# Busboard_SCH.net
KiCad netlist of a schematic drawn in Altium Designer
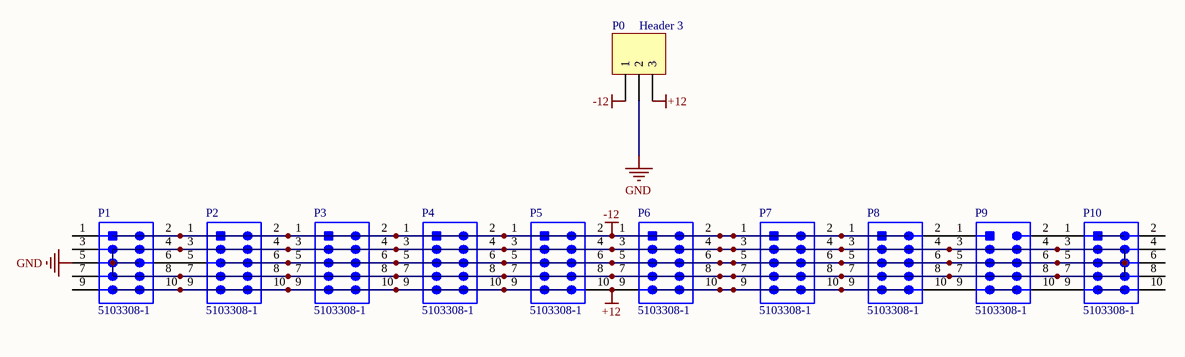
[diagram p0: Busboard_SCH.SchDoc]

(export (version "E")
  (design (tool "Eeschema 10.0.6"))
  (components
    (comp (ref "P0")
      (value "Header 3")
      (footprint "HDR1X3")
      (description "Header, 3-Pin")
      (fields (field (name "PUBLISHER") "Altium Limited"))
      (libsource (lib "Miscellaneous Connectors") (part "Header 3"))
    )
    (comp (ref "P1")
      (value "5103308-1")
      (footprint "TECO-5103308-1_V")
      (description "Male Header, Pitch 2.54 mm, 2 x 5 Position, Height 9.85 mm, Tail Length 3.05 mm, RoHS, Tube")
      (fields (field (name "MANUFACTURER") "TE Connectivity"))
      (libsource (lib "Altium Content Vault") (part "CN-2P-M-R10"))
    )
    (comp (ref "P2")
      (value "5103308-1")
      (footprint "TECO-5103308-1_V")
      (description "Male Header, Pitch 2.54 mm, 2 x 5 Position, Height 9.85 mm, Tail Length 3.05 mm, RoHS, Tube")
      (fields (field (name "MANUFACTURER") "TE Connectivity"))
      (libsource (lib "Altium Content Vault") (part "CN-2P-M-R10"))
    )
    (comp (ref "P3")
      (value "5103308-1")
      (footprint "TECO-5103308-1_V")
      (description "Male Header, Pitch 2.54 mm, 2 x 5 Position, Height 9.85 mm, Tail Length 3.05 mm, RoHS, Tube")
      (fields (field (name "MANUFACTURER") "TE Connectivity"))
      (libsource (lib "Altium Content Vault") (part "CN-2P-M-R10"))
    )
    (comp (ref "P4")
      (value "5103308-1")
      (footprint "TECO-5103308-1_V")
      (description "Male Header, Pitch 2.54 mm, 2 x 5 Position, Height 9.85 mm, Tail Length 3.05 mm, RoHS, Tube")
      (fields (field (name "MANUFACTURER") "TE Connectivity"))
      (libsource (lib "Altium Content Vault") (part "CN-2P-M-R10"))
    )
    (comp (ref "P5")
      (value "5103308-1")
      (footprint "TECO-5103308-1_V")
      (description "Male Header, Pitch 2.54 mm, 2 x 5 Position, Height 9.85 mm, Tail Length 3.05 mm, RoHS, Tube")
      (fields (field (name "MANUFACTURER") "TE Connectivity"))
      (libsource (lib "Altium Content Vault") (part "CN-2P-M-R10"))
    )
    (comp (ref "P6")
      (value "5103308-1")
      (footprint "TECO-5103308-1_V")
      (description "Male Header, Pitch 2.54 mm, 2 x 5 Position, Height 9.85 mm, Tail Length 3.05 mm, RoHS, Tube")
      (fields (field (name "MANUFACTURER") "TE Connectivity"))
      (libsource (lib "Altium Content Vault") (part "CN-2P-M-R10"))
    )
    (comp (ref "P7")
      (value "5103308-1")
      (footprint "TECO-5103308-1_V")
      (description "Male Header, Pitch 2.54 mm, 2 x 5 Position, Height 9.85 mm, Tail Length 3.05 mm, RoHS, Tube")
      (fields (field (name "MANUFACTURER") "TE Connectivity"))
      (libsource (lib "Altium Content Vault") (part "CN-2P-M-R10"))
    )
    (comp (ref "P8")
      (value "5103308-1")
      (footprint "TECO-5103308-1_V")
      (description "Male Header, Pitch 2.54 mm, 2 x 5 Position, Height 9.85 mm, Tail Length 3.05 mm, RoHS, Tube")
      (fields (field (name "MANUFACTURER") "TE Connectivity"))
      (libsource (lib "Altium Content Vault") (part "CN-2P-M-R10"))
    )
    (comp (ref "P9")
      (value "5103308-1")
      (footprint "TECO-5103308-1_V")
      (description "Male Header, Pitch 2.54 mm, 2 x 5 Position, Height 9.85 mm, Tail Length 3.05 mm, RoHS, Tube")
      (fields (field (name "MANUFACTURER") "TE Connectivity"))
      (libsource (lib "Altium Content Vault") (part "CN-2P-M-R10"))
    )
    (comp (ref "P10")
      (value "5103308-1")
      (footprint "TECO-5103308-1_V")
      (description "Male Header, Pitch 2.54 mm, 2 x 5 Position, Height 9.85 mm, Tail Length 3.05 mm, RoHS, Tube")
      (fields (field (name "MANUFACTURER") "TE Connectivity"))
      (libsource (lib "Altium Content Vault") (part "CN-2P-M-R10"))
    )
  )
  (nets
    (net (code "1") (name "+12") (class "Default")
      (node (ref "P0") (pin "3") (pinfunction "3_3") (pintype "passive"))
      (node (ref "P5") (pin "10") (pinfunction "10_10") (pintype "passive"))
      (node (ref "P6") (pin "9") (pinfunction "9_9") (pintype "passive"))
    )
    (net (code "2") (name "-12") (class "Default")
      (node (ref "P0") (pin "1") (pinfunction "1_1") (pintype "passive"))
      (node (ref "P1") (pin "2") (pinfunction "2_2") (pintype "passive"))
      (node (ref "P2") (pin "1") (pinfunction "1_1") (pintype "passive"))
      (node (ref "P2") (pin "2") (pinfunction "2_2") (pintype "passive"))
      (node (ref "P3") (pin "1") (pinfunction "1_1") (pintype "passive"))
      (node (ref "P3") (pin "2") (pinfunction "2_2") (pintype "passive"))
      (node (ref "P4") (pin "1") (pinfunction "1_1") (pintype "passive"))
      (node (ref "P4") (pin "2") (pinfunction "2_2") (pintype "passive"))
      (node (ref "P5") (pin "1") (pinfunction "1_1") (pintype "passive"))
      (node (ref "P5") (pin "2") (pinfunction "2_2") (pintype "passive"))
      (node (ref "P6") (pin "1") (pinfunction "1_1") (pintype "passive"))
      (node (ref "P6") (pin "2") (pinfunction "2_2") (pintype "passive"))
      (node (ref "P7") (pin "1") (pinfunction "1_1") (pintype "passive"))
      (node (ref "P7") (pin "2") (pinfunction "2_2") (pintype "passive"))
      (node (ref "P8") (pin "1") (pinfunction "1_1") (pintype "passive"))
    )
    (net (code "3") (name "GND") (class "Default")
      (node (ref "P0") (pin "2") (pinfunction "2_2") (pintype "passive"))
      (node (ref "P1") (pin "5") (pinfunction "5_5") (pintype "passive"))
    )
    (net (code "4") (name "Net-(P1-Pad4)") (class "Default")
      (node (ref "P1") (pin "4") (pinfunction "4_4") (pintype "passive"))
      (node (ref "P1") (pin "8") (pinfunction "8_8") (pintype "passive"))
      (node (ref "P10") (pin "3") (pinfunction "3_3") (pintype "passive"))
      (node (ref "P10") (pin "5") (pinfunction "5_5") (pintype "passive"))
      (node (ref "P10") (pin "7") (pinfunction "7_7") (pintype "passive"))
      (node (ref "P2") (pin "3") (pinfunction "3_3") (pintype "passive"))
      (node (ref "P2") (pin "4") (pinfunction "4_4") (pintype "passive"))
      (node (ref "P2") (pin "6") (pinfunction "6_6") (pintype "passive"))
      (node (ref "P2") (pin "7") (pinfunction "7_7") (pintype "passive"))
      (node (ref "P2") (pin "8") (pinfunction "8_8") (pintype "passive"))
      (node (ref "P3") (pin "3") (pinfunction "3_3") (pintype "passive"))
      (node (ref "P3") (pin "4") (pinfunction "4_4") (pintype "passive"))
      (node (ref "P3") (pin "5") (pinfunction "5_5") (pintype "passive"))
      (node (ref "P3") (pin "6") (pinfunction "6_6") (pintype "passive"))
      (node (ref "P3") (pin "7") (pinfunction "7_7") (pintype "passive"))
      (node (ref "P3") (pin "8") (pinfunction "8_8") (pintype "passive"))
      (node (ref "P4") (pin "3") (pinfunction "3_3") (pintype "passive"))
      (node (ref "P4") (pin "4") (pinfunction "4_4") (pintype "passive"))
      (node (ref "P4") (pin "5") (pinfunction "5_5") (pintype "passive"))
      (node (ref "P4") (pin "6") (pinfunction "6_6") (pintype "passive"))
      (node (ref "P4") (pin "7") (pinfunction "7_7") (pintype "passive"))
      (node (ref "P4") (pin "8") (pinfunction "8_8") (pintype "passive"))
      (node (ref "P5") (pin "3") (pinfunction "3_3") (pintype "passive"))
      (node (ref "P5") (pin "4") (pinfunction "4_4") (pintype "passive"))
      (node (ref "P5") (pin "5") (pinfunction "5_5") (pintype "passive"))
      (node (ref "P5") (pin "6") (pinfunction "6_6") (pintype "passive"))
      (node (ref "P5") (pin "7") (pinfunction "7_7") (pintype "passive"))
      (node (ref "P5") (pin "8") (pinfunction "8_8") (pintype "passive"))
      (node (ref "P6") (pin "3") (pinfunction "3_3") (pintype "passive"))
      (node (ref "P6") (pin "4") (pinfunction "4_4") (pintype "passive"))
      (node (ref "P6") (pin "5") (pinfunction "5_5") (pintype "passive"))
      (node (ref "P6") (pin "6") (pinfunction "6_6") (pintype "passive"))
      (node (ref "P6") (pin "7") (pinfunction "7_7") (pintype "passive"))
      (node (ref "P6") (pin "8") (pinfunction "8_8") (pintype "passive"))
      (node (ref "P7") (pin "3") (pinfunction "3_3") (pintype "passive"))
      (node (ref "P7") (pin "4") (pinfunction "4_4") (pintype "passive"))
      (node (ref "P7") (pin "5") (pinfunction "5_5") (pintype "passive"))
      (node (ref "P7") (pin "6") (pinfunction "6_6") (pintype "passive"))
      (node (ref "P7") (pin "7") (pinfunction "7_7") (pintype "passive"))
      (node (ref "P7") (pin "8") (pinfunction "8_8") (pintype "passive"))
      (node (ref "P8") (pin "3") (pinfunction "3_3") (pintype "passive"))
      (node (ref "P8") (pin "4") (pinfunction "4_4") (pintype "passive"))
      (node (ref "P8") (pin "5") (pinfunction "5_5") (pintype "passive"))
      (node (ref "P8") (pin "6") (pinfunction "6_6") (pintype "passive"))
      (node (ref "P8") (pin "7") (pinfunction "7_7") (pintype "passive"))
      (node (ref "P8") (pin "8") (pinfunction "8_8") (pintype "passive"))
      (node (ref "P9") (pin "3") (pinfunction "3_3") (pintype "passive"))
      (node (ref "P9") (pin "4") (pinfunction "4_4") (pintype "passive"))
      (node (ref "P9") (pin "5") (pinfunction "5_5") (pintype "passive"))
      (node (ref "P9") (pin "6") (pinfunction "6_6") (pintype "passive"))
      (node (ref "P9") (pin "7") (pinfunction "7_7") (pintype "passive"))
      (node (ref "P9") (pin "8") (pinfunction "8_8") (pintype "passive"))
    )
    (net (code "5") (name "Net-(P1-Pad6)") (class "Default")
      (node (ref "P1") (pin "6") (pinfunction "6_6") (pintype "passive"))
      (node (ref "P2") (pin "5") (pinfunction "5_5") (pintype "passive"))
    )
    (net (code "6") (name "Net-(P1-Pad10)") (class "Default")
      (node (ref "P1") (pin "10") (pinfunction "10_10") (pintype "passive"))
      (node (ref "P2") (pin "10") (pinfunction "10_10") (pintype "passive"))
      (node (ref "P2") (pin "9") (pinfunction "9_9") (pintype "passive"))
      (node (ref "P3") (pin "10") (pinfunction "10_10") (pintype "passive"))
      (node (ref "P3") (pin "9") (pinfunction "9_9") (pintype "passive"))
      (node (ref "P4") (pin "10") (pinfunction "10_10") (pintype "passive"))
      (node (ref "P4") (pin "9") (pinfunction "9_9") (pintype "passive"))
      (node (ref "P5") (pin "9") (pinfunction "9_9") (pintype "passive"))
    )
    (net (code "7") (name "Net-(P6-Pad10)") (class "Default")
      (node (ref "P6") (pin "10") (pinfunction "10_10") (pintype "passive"))
      (node (ref "P7") (pin "10") (pinfunction "10_10") (pintype "passive"))
      (node (ref "P7") (pin "9") (pinfunction "9_9") (pintype "passive"))
      (node (ref "P8") (pin "9") (pinfunction "9_9") (pintype "passive"))
    )
    (net (code "8") (name "Net-(P8-Pad2)") (class "Default")
      (node (ref "P8") (pin "2") (pinfunction "2_2") (pintype "passive"))
      (node (ref "P9") (pin "1") (pinfunction "1_1") (pintype "passive"))
    )
    (net (code "9") (name "Net-(P8-Pad10)") (class "Default")
      (node (ref "P8") (pin "10") (pinfunction "10_10") (pintype "passive"))
      (node (ref "P9") (pin "9") (pinfunction "9_9") (pintype "passive"))
    )
    (net (code "10") (name "Net-(P10-Pad1)") (class "Default")
      (node (ref "P10") (pin "1") (pinfunction "1_1") (pintype "passive"))
      (node (ref "P9") (pin "2") (pinfunction "2_2") (pintype "passive"))
    )
    (net (code "11") (name "Net-(P10-Pad9)") (class "Default")
      (node (ref "P10") (pin "9") (pinfunction "9_9") (pintype "passive"))
      (node (ref "P9") (pin "10") (pinfunction "10_10") (pintype "passive"))
    )
    (net (code "12") (name "unconnected-(P1-Pad1)") (class "Default")
      (node (ref "P1") (pin "1") (pinfunction "1_1") (pintype "passive"))
    )
    (net (code "13") (name "unconnected-(P1-Pad3)") (class "Default")
      (node (ref "P1") (pin "3") (pinfunction "3_3") (pintype "passive"))
    )
    (net (code "14") (name "unconnected-(P1-Pad7)") (class "Default")
      (node (ref "P1") (pin "7") (pinfunction "7_7") (pintype "passive"))
    )
    (net (code "15") (name "unconnected-(P1-Pad9)") (class "Default")
      (node (ref "P1") (pin "9") (pinfunction "9_9") (pintype "passive"))
    )
    (net (code "16") (name "unconnected-(P10-Pad2)") (class "Default")
      (node (ref "P10") (pin "2") (pinfunction "2_2") (pintype "passive"))
    )
    (net (code "17") (name "unconnected-(P10-Pad4)") (class "Default")
      (node (ref "P10") (pin "4") (pinfunction "4_4") (pintype "passive"))
    )
    (net (code "18") (name "unconnected-(P10-Pad6)") (class "Default")
      (node (ref "P10") (pin "6") (pinfunction "6_6") (pintype "passive"))
    )
    (net (code "19") (name "unconnected-(P10-Pad8)") (class "Default")
      (node (ref "P10") (pin "8") (pinfunction "8_8") (pintype "passive"))
    )
    (net (code "20") (name "unconnected-(P10-Pad10)") (class "Default")
      (node (ref "P10") (pin "10") (pinfunction "10_10") (pintype "passive"))
    )
  )
)
